# openSX70-dongle_v3-8.net
KiCad netlist of a schematic drawn in EAGLE
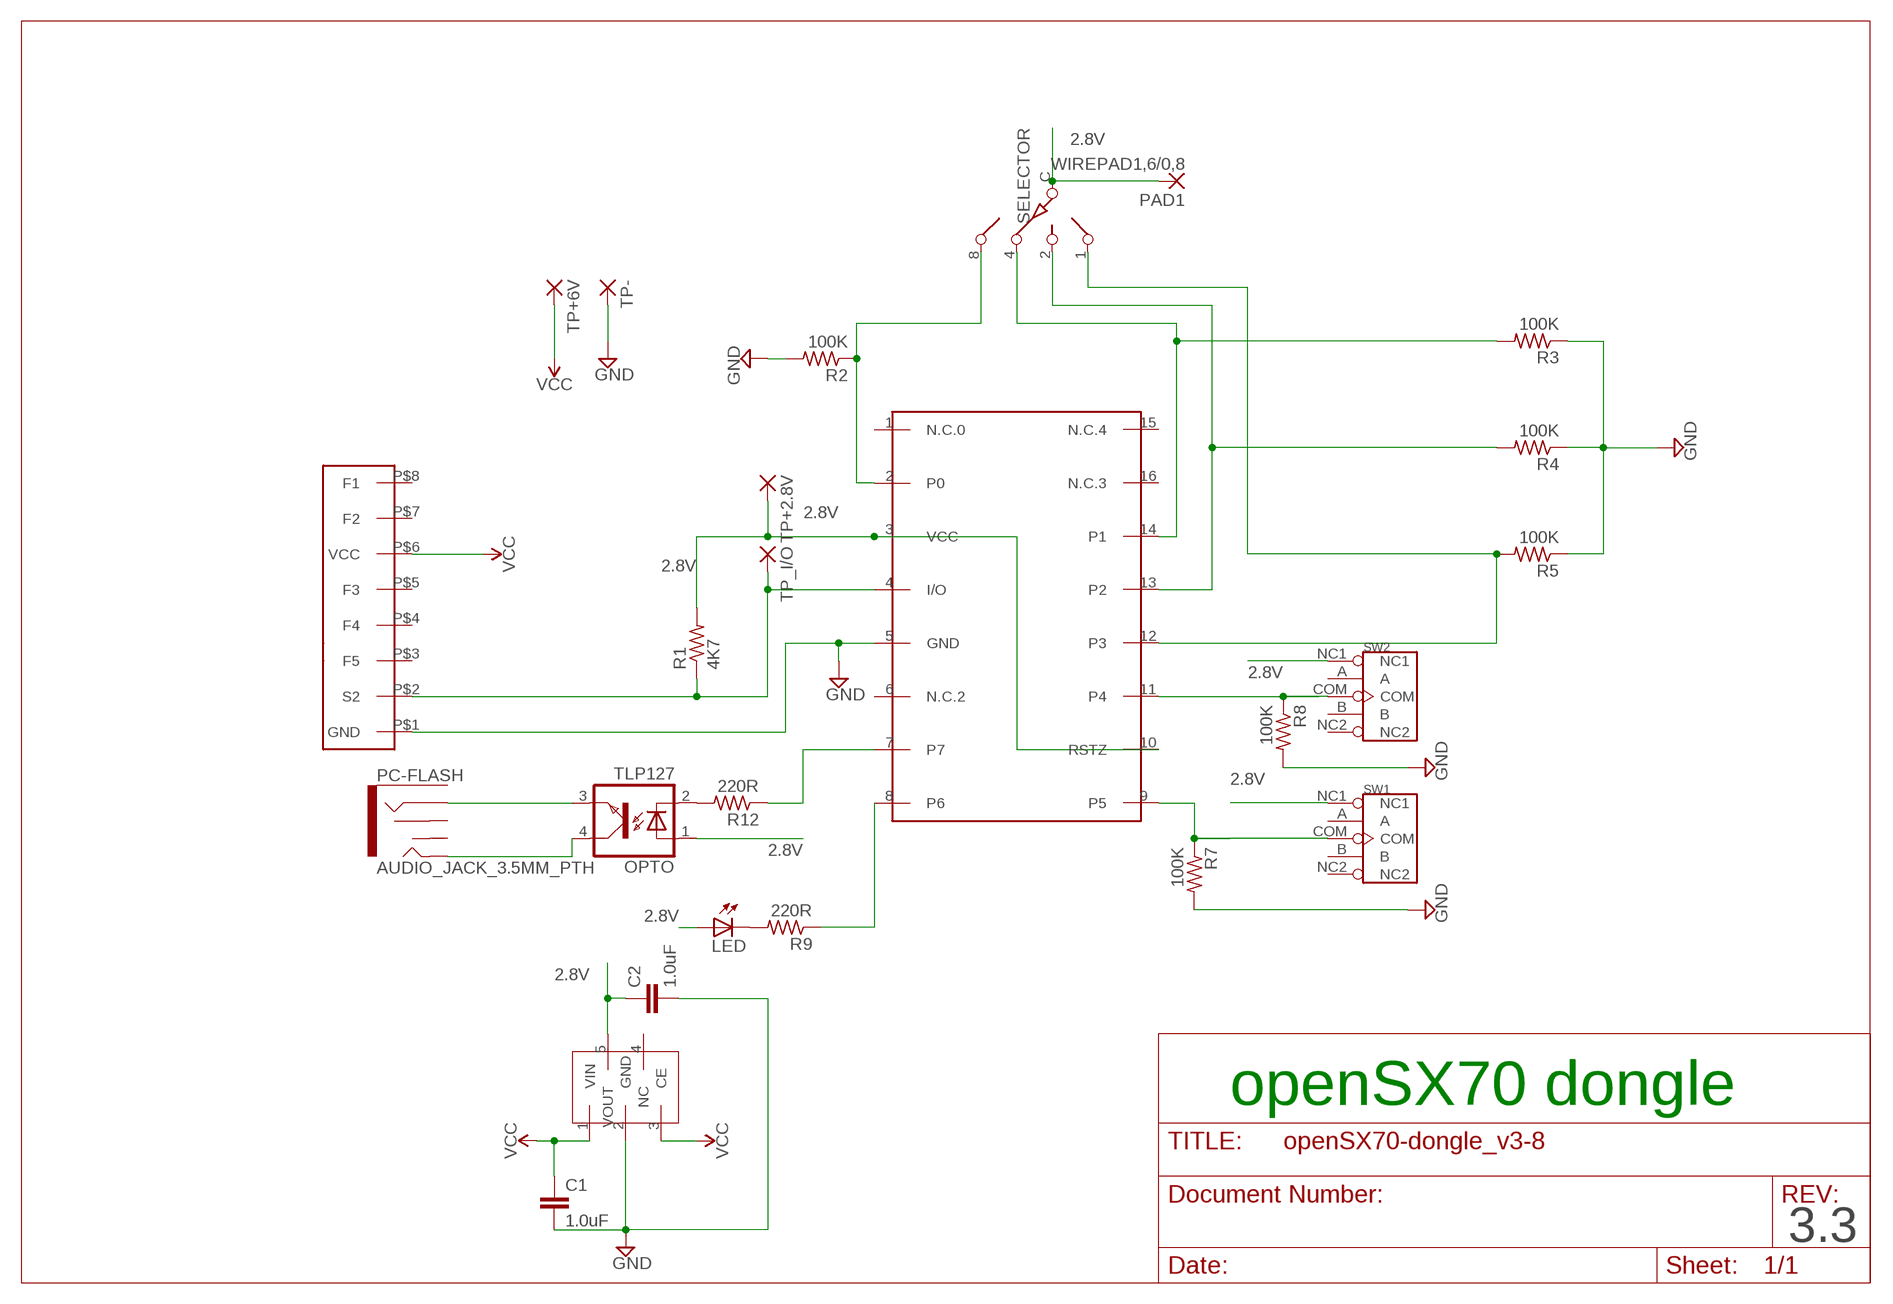
[diagram p0: schematic, sheet 1]

(export (version "E")
  (design (tool "Eeschema 10.0.6"))
  (components
    (comp (ref "C1")
      (value "1.0uF")
      (footprint "eagle-import:C0603")
      (libsource (lib "eagle-import") (part "C-EUC0603"))
    )
    (comp (ref "C2")
      (value "1.0uF")
      (footprint "eagle-import:C0603")
      (libsource (lib "eagle-import") (part "C-EUC0603"))
    )
    (comp (ref "DS2408")
      (value "DS2408")
      (footprint "eagle-import:SO16")
      (libsource (lib "eagle-import") (part "DS2408"))
    )
    (comp (ref "LED")
      (value "LED3MM")
      (footprint "eagle-import:LED3MM")
      (libsource (lib "eagle-import") (part "LED3MM"))
    )
    (comp (ref "OPTO")
      (value "TLP127")
      (footprint "eagle-import:SO-4")
      (libsource (lib "eagle-import") (part "TLP127"))
    )
    (comp (ref "PAD1")
      (value "WIREPAD1,6/0,8")
      (footprint "eagle-import:1,6_0,8")
      (libsource (lib "eagle-import") (part "WIREPAD1,6/0,8"))
    )
    (comp (ref "PC-FLASH")
      (value "AUDIO_JACK_3.5MM_PTH")
      (footprint "eagle-import:AUDIO-JACK")
      (libsource (lib "eagle-import") (part "AUDIO_JACK_3.5MM_PTH"))
    )
    (comp (ref "R1")
      (value "4K7")
      (footprint "eagle-import:M0805")
      (libsource (lib "eagle-import") (part "R-US_M0805"))
    )
    (comp (ref "R2")
      (value "100K")
      (footprint "eagle-import:M0805")
      (libsource (lib "eagle-import") (part "R-US_M0805"))
    )
    (comp (ref "R3")
      (value "100K")
      (footprint "eagle-import:M0805")
      (libsource (lib "eagle-import") (part "R-US_M0805"))
    )
    (comp (ref "R4")
      (value "100K")
      (footprint "eagle-import:M0805")
      (libsource (lib "eagle-import") (part "R-US_M0805"))
    )
    (comp (ref "R5")
      (value "100K")
      (footprint "eagle-import:M0805")
      (libsource (lib "eagle-import") (part "R-US_M0805"))
    )
    (comp (ref "R7")
      (value "100K")
      (footprint "eagle-import:M0805")
      (libsource (lib "eagle-import") (part "R-US_M0805"))
    )
    (comp (ref "R8")
      (value "100K")
      (footprint "eagle-import:M0805")
      (libsource (lib "eagle-import") (part "R-US_M0805"))
    )
    (comp (ref "R9")
      (value "220R")
      (footprint "eagle-import:M0805")
      (libsource (lib "eagle-import") (part "R-US_M0805"))
    )
    (comp (ref "R12")
      (value "220R")
      (footprint "eagle-import:M0805")
      (libsource (lib "eagle-import") (part "R-US_M0805"))
    )
    (comp (ref "REG")
      (value "NCP4688")
      (footprint "eagle-import:SOT-23-5")
      (libsource (lib "eagle-import") (part "NCP4688"))
    )
    (comp (ref "SELECTOR")
      (value "SW-C16")
      (footprint "eagle-import:SW-C16")
      (libsource (lib "eagle-import") (part "SW-C16"))
    )
    (comp (ref "SW1")
      (value "DIP-TOGGLE-SWITCH-ON-ON(3+2P-8.8X4.6MM)-90D")
      (footprint "eagle-import:SW5-2.0-8.8X4.4X4.7MM-90D")
      (fields (field (name "MPN") "3P-2.0-90D3P-2.0-90D-REINFORCE"))
      (libsource (lib "eagle-import") (part "DIP-TOGGLE-SWITCH-ON-ON(3+2P-8.8X4.6MM)-90D"))
    )
    (comp (ref "SW2")
      (value "DIP-TOGGLE-SWITCH-ON-ON(3+2P-8.8X4.6MM)-90D")
      (footprint "eagle-import:SW5-2.0-8.8X4.4X4.7MM-90D")
      (fields (field (name "MPN") "3P-2.0-90D3P-2.0-90D-REINFORCE"))
      (libsource (lib "eagle-import") (part "DIP-TOGGLE-SWITCH-ON-ON(3+2P-8.8X4.6MM)-90D"))
    )
    (comp (ref "TP+2.8V")
      (value "SMD2")
      (footprint "eagle-import:SMD1,27-2,54")
      (libsource (lib "eagle-import") (part "SMD2"))
    )
    (comp (ref "TP+6V")
      (value "SMD2")
      (footprint "eagle-import:SMD1,27-2,54")
      (libsource (lib "eagle-import") (part "SMD2"))
    )
    (comp (ref "TP-")
      (value "SMD2")
      (footprint "eagle-import:SMD1,27-2,54")
      (libsource (lib "eagle-import") (part "SMD2"))
    )
    (comp (ref "TP_I/O")
      (value "SMD2")
      (footprint "eagle-import:SMD1,27-2,54")
      (libsource (lib "eagle-import") (part "SMD2"))
    )
    (comp (ref "U$1")
      (value "FLASH-EDGE-CONNECTOR")
      (footprint "eagle-import:FLASH-EDGE-8")
      (libsource (lib "eagle-import") (part "FLASH-EDGE-CONNECTOR"))
    )
  )
  (nets
    (net (code "1") (name "/2.8V") (class "Default")
      (node (ref "C2") (pin "1") (pinfunction "1_1") (pintype "passive"))
      (node (ref "DS2408") (pin "10") (pinfunction "RSTZ_10") (pintype "bidirectional"))
      (node (ref "DS2408") (pin "3") (pinfunction "VCC_3") (pintype "bidirectional"))
      (node (ref "LED") (pin "A") (pinfunction "A_A") (pintype "passive"))
      (node (ref "OPTO") (pin "1") (pinfunction "A_1") (pintype "passive"))
      (node (ref "PAD1") (pin "1") (pinfunction "P_1") (pintype "passive"))
      (node (ref "R1") (pin "2") (pinfunction "2_2") (pintype "passive"))
      (node (ref "REG") (pin "5") (pinfunction "VOUT_5") (pintype "bidirectional"))
      (node (ref "SELECTOR") (pin "C") (pinfunction "C_C") (pintype "passive"))
      (node (ref "SW1") (pin "NC1") (pinfunction "NC1_NC1") (pintype "bidirectional"))
      (node (ref "SW2") (pin "NC1") (pinfunction "NC1_NC1") (pintype "bidirectional"))
      (node (ref "TP+2.8V") (pin "1") (pinfunction "P_1") (pintype "passive"))
    )
    (net (code "2") (name "GND") (class "Default")
      (node (ref "C1") (pin "2") (pinfunction "2_2") (pintype "passive"))
      (node (ref "C2") (pin "2") (pinfunction "2_2") (pintype "passive"))
      (node (ref "DS2408") (pin "5") (pinfunction "GND_5") (pintype "bidirectional"))
      (node (ref "R2") (pin "2") (pinfunction "2_2") (pintype "passive"))
      (node (ref "R3") (pin "1") (pinfunction "1_1") (pintype "passive"))
      (node (ref "R4") (pin "1") (pinfunction "1_1") (pintype "passive"))
      (node (ref "R5") (pin "1") (pinfunction "1_1") (pintype "passive"))
      (node (ref "R7") (pin "2") (pinfunction "2_2") (pintype "passive"))
      (node (ref "R8") (pin "2") (pinfunction "2_2") (pintype "passive"))
      (node (ref "REG") (pin "2") (pinfunction "GND_2") (pintype "bidirectional"))
      (node (ref "TP-") (pin "1") (pinfunction "P_1") (pintype "passive"))
      (node (ref "U$1") (pin "P$1") (pinfunction "GND_P$1") (pintype "bidirectional"))
    )
    (net (code "3") (name "Net-(DS2408-I{slash}O)") (class "Default")
      (node (ref "DS2408") (pin "4") (pinfunction "I/O_4") (pintype "bidirectional"))
      (node (ref "R1") (pin "1") (pinfunction "1_1") (pintype "passive"))
      (node (ref "TP_I/O") (pin "1") (pinfunction "P_1") (pintype "passive"))
      (node (ref "U$1") (pin "P$2") (pinfunction "S2_P$2") (pintype "bidirectional"))
    )
    (net (code "4") (name "Net-(DS2408-P0)") (class "Default")
      (node (ref "DS2408") (pin "2") (pinfunction "P0_2") (pintype "bidirectional"))
      (node (ref "R2") (pin "1") (pinfunction "1_1") (pintype "passive"))
      (node (ref "SELECTOR") (pin "8") (pinfunction "8_8") (pintype "passive"))
    )
    (net (code "5") (name "Net-(DS2408-P1)") (class "Default")
      (node (ref "DS2408") (pin "14") (pinfunction "P1_14") (pintype "bidirectional"))
      (node (ref "R3") (pin "2") (pinfunction "2_2") (pintype "passive"))
      (node (ref "SELECTOR") (pin "4") (pinfunction "4_4") (pintype "passive"))
    )
    (net (code "6") (name "Net-(DS2408-P2)") (class "Default")
      (node (ref "DS2408") (pin "13") (pinfunction "P2_13") (pintype "bidirectional"))
      (node (ref "R4") (pin "2") (pinfunction "2_2") (pintype "passive"))
      (node (ref "SELECTOR") (pin "2") (pinfunction "2_2") (pintype "passive"))
    )
    (net (code "7") (name "Net-(DS2408-P3)") (class "Default")
      (node (ref "DS2408") (pin "12") (pinfunction "P3_12") (pintype "bidirectional"))
      (node (ref "R5") (pin "2") (pinfunction "2_2") (pintype "passive"))
      (node (ref "SELECTOR") (pin "1") (pinfunction "1_1") (pintype "passive"))
    )
    (net (code "8") (name "Net-(DS2408-P4)") (class "Default")
      (node (ref "DS2408") (pin "11") (pinfunction "P4_11") (pintype "bidirectional"))
      (node (ref "R8") (pin "1") (pinfunction "1_1") (pintype "passive"))
      (node (ref "SW2") (pin "COM") (pinfunction "COM_COM") (pintype "bidirectional"))
    )
    (net (code "9") (name "Net-(DS2408-P5)") (class "Default")
      (node (ref "DS2408") (pin "9") (pinfunction "P5_9") (pintype "bidirectional"))
      (node (ref "R7") (pin "1") (pinfunction "1_1") (pintype "passive"))
      (node (ref "SW1") (pin "COM") (pinfunction "COM_COM") (pintype "bidirectional"))
    )
    (net (code "10") (name "Net-(DS2408-P6)") (class "Default")
      (node (ref "DS2408") (pin "8") (pinfunction "P6_8") (pintype "bidirectional"))
      (node (ref "R9") (pin "1") (pinfunction "1_1") (pintype "passive"))
    )
    (net (code "11") (name "Net-(DS2408-P7)") (class "Default")
      (node (ref "DS2408") (pin "7") (pinfunction "P7_7") (pintype "bidirectional"))
      (node (ref "R12") (pin "1") (pinfunction "1_1") (pintype "passive"))
    )
    (net (code "12") (name "Net-(LED-C)") (class "Default")
      (node (ref "LED") (pin "K") (pinfunction "C_K") (pintype "passive"))
      (node (ref "R9") (pin "2") (pinfunction "2_2") (pintype "passive"))
    )
    (net (code "13") (name "Net-(OPTO-C)") (class "Default")
      (node (ref "OPTO") (pin "2") (pinfunction "C_2") (pintype "passive"))
      (node (ref "R12") (pin "2") (pinfunction "2_2") (pintype "passive"))
    )
    (net (code "14") (name "Net-(OPTO-COL)") (class "Default")
      (node (ref "OPTO") (pin "4") (pinfunction "COL_4") (pintype "passive"))
      (node (ref "PC-FLASH") (pin "TIP") (pinfunction "TIP_TIP") (pintype "bidirectional"))
    )
    (net (code "15") (name "Net-(OPTO-EMIT)") (class "Default")
      (node (ref "OPTO") (pin "3") (pinfunction "EMIT_3") (pintype "passive"))
      (node (ref "PC-FLASH") (pin "RING") (pinfunction "RING_RING") (pintype "bidirectional"))
    )
    (net (code "16") (name "VCC") (class "Default")
      (node (ref "C1") (pin "1") (pinfunction "1_1") (pintype "passive"))
      (node (ref "REG") (pin "1") (pinfunction "VIN_1") (pintype "bidirectional"))
      (node (ref "REG") (pin "3") (pinfunction "CE_3") (pintype "bidirectional"))
      (node (ref "TP+6V") (pin "1") (pinfunction "P_1") (pintype "passive"))
      (node (ref "U$1") (pin "P$6") (pinfunction "VCC_P$6") (pintype "bidirectional"))
    )
    (net (code "17") (name "unconnected-(DS2408-N.C.0-Pad1)") (class "Default")
      (node (ref "DS2408") (pin "1") (pinfunction "N.C.0_1") (pintype "bidirectional"))
    )
    (net (code "18") (name "unconnected-(DS2408-N.C.2-Pad6)") (class "Default")
      (node (ref "DS2408") (pin "6") (pinfunction "N.C.2_6") (pintype "bidirectional"))
    )
    (net (code "19") (name "unconnected-(DS2408-N.C.3-Pad16)") (class "Default")
      (node (ref "DS2408") (pin "16") (pinfunction "N.C.3_16") (pintype "bidirectional"))
    )
    (net (code "20") (name "unconnected-(DS2408-N.C.4-Pad15)") (class "Default")
      (node (ref "DS2408") (pin "15") (pinfunction "N.C.4_15") (pintype "bidirectional"))
    )
    (net (code "21") (name "unconnected-(PC-FLASH-PadRSH)") (class "Default")
      (node (ref "PC-FLASH") (pin "RSH") (pinfunction "RSH_RSH") (pintype "bidirectional"))
    )
    (net (code "22") (name "unconnected-(PC-FLASH-PadSLEEVE)") (class "Default")
      (node (ref "PC-FLASH") (pin "SLEEVE") (pinfunction "SLEEVE_SLEEVE") (pintype "bidirectional"))
    )
    (net (code "23") (name "unconnected-(PC-FLASH-PadTSH)") (class "Default")
      (node (ref "PC-FLASH") (pin "TSH") (pinfunction "TSH_TSH") (pintype "bidirectional"))
    )
    (net (code "24") (name "unconnected-(REG-NC-Pad4)") (class "Default")
      (node (ref "REG") (pin "4") (pinfunction "NC_4") (pintype "bidirectional"))
    )
    (net (code "25") (name "unconnected-(SW1-PadA)") (class "Default")
      (node (ref "SW1") (pin "A") (pinfunction "A_A") (pintype "bidirectional"))
    )
    (net (code "26") (name "unconnected-(SW1-PadB)") (class "Default")
      (node (ref "SW1") (pin "B") (pinfunction "B_B") (pintype "bidirectional"))
    )
    (net (code "27") (name "unconnected-(SW1-PadNC2)") (class "Default")
      (node (ref "SW1") (pin "NC2") (pinfunction "NC2_NC2") (pintype "bidirectional"))
    )
    (net (code "28") (name "unconnected-(SW2-PadA)") (class "Default")
      (node (ref "SW2") (pin "A") (pinfunction "A_A") (pintype "bidirectional"))
    )
    (net (code "29") (name "unconnected-(SW2-PadB)") (class "Default")
      (node (ref "SW2") (pin "B") (pinfunction "B_B") (pintype "bidirectional"))
    )
    (net (code "30") (name "unconnected-(SW2-PadNC2)") (class "Default")
      (node (ref "SW2") (pin "NC2") (pinfunction "NC2_NC2") (pintype "bidirectional"))
    )
    (net (code "31") (name "unconnected-(U$1-F1-PadP$8)") (class "Default")
      (node (ref "U$1") (pin "P$8") (pinfunction "F1_P$8") (pintype "bidirectional"))
    )
    (net (code "32") (name "unconnected-(U$1-F2-PadP$7)") (class "Default")
      (node (ref "U$1") (pin "P$7") (pinfunction "F2_P$7") (pintype "bidirectional"))
    )
    (net (code "33") (name "unconnected-(U$1-F3-PadP$5)") (class "Default")
      (node (ref "U$1") (pin "P$5") (pinfunction "F3_P$5") (pintype "bidirectional"))
    )
    (net (code "34") (name "unconnected-(U$1-F4-PadP$4)") (class "Default")
      (node (ref "U$1") (pin "P$4") (pinfunction "F4_P$4") (pintype "bidirectional"))
    )
    (net (code "35") (name "unconnected-(U$1-F5-PadP$3)") (class "Default")
      (node (ref "U$1") (pin "P$3") (pinfunction "F5_P$3") (pintype "bidirectional"))
    )
  )
)
